# HAB.net
KiCad netlist of a schematic drawn in EAGLE
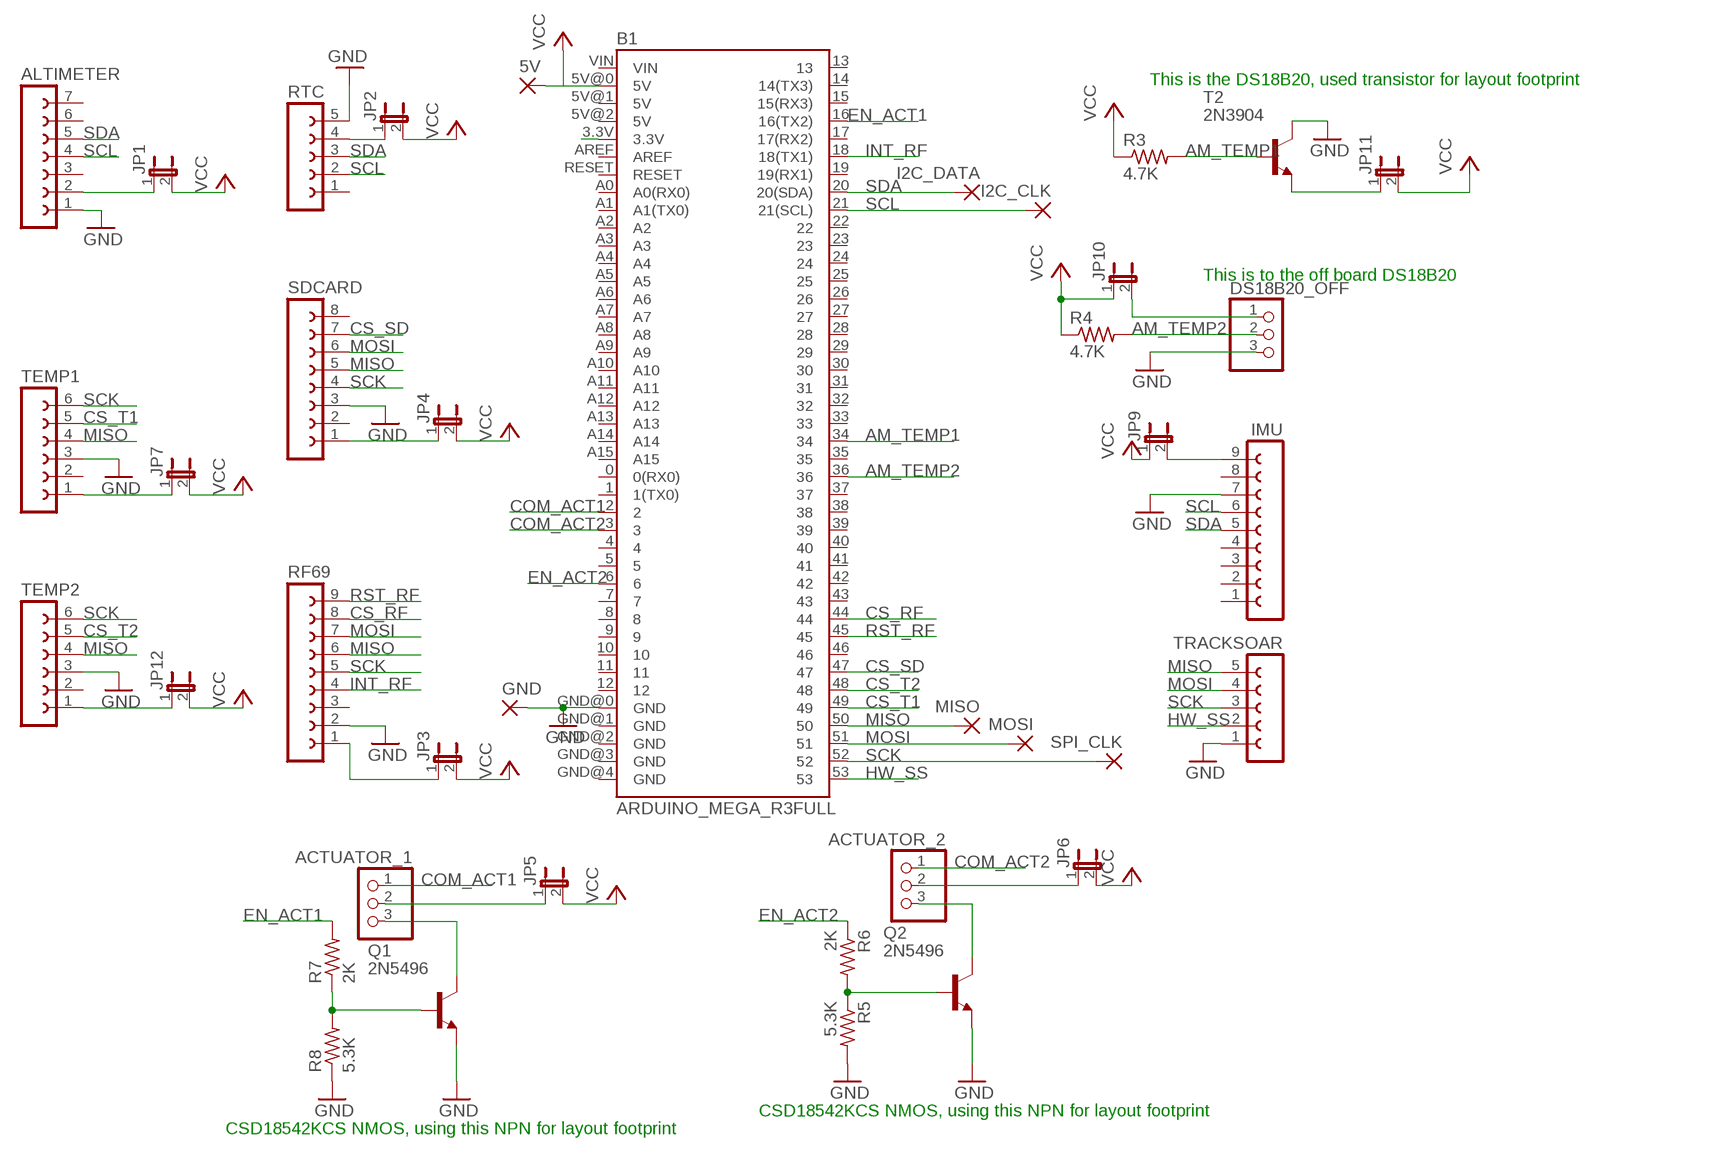
[diagram p0: schematic, sheet 1]

(export (version "E")
  (design (tool "Eeschema 10.0.6"))
  (components
    (comp (ref "5V")
      (value "1,6/0,8")
      (footprint "eagle-import:1,6_0,8")
      (libsource (lib "eagle-import") (part "1,6/0,8"))
    )
    (comp (ref "ACTUATOR_1")
      (value "PINHD-1X3")
      (footprint "eagle-import:1X03")
      (libsource (lib "eagle-import") (part "PINHD-1X3"))
    )
    (comp (ref "ACTUATOR_2")
      (value "PINHD-1X3")
      (footprint "eagle-import:1X03")
      (libsource (lib "eagle-import") (part "PINHD-1X3"))
    )
    (comp (ref "ALTIMETER")
      (value "FE07-1")
      (footprint "eagle-import:FE07")
      (libsource (lib "eagle-import") (part "FE07-1"))
    )
    (comp (ref "B1")
      (value "ARDUINO_MEGA_R3FULL")
      (footprint "eagle-import:ARDUINO_MEGA")
      (libsource (lib "eagle-import") (part "ARDUINO_MEGA_R3FULL"))
    )
    (comp (ref "DS18B20_OFF")
      (value "PINHD-1X3")
      (footprint "eagle-import:1X03")
      (libsource (lib "eagle-import") (part "PINHD-1X3"))
    )
    (comp (ref "GND")
      (value "1,6/0,8")
      (footprint "eagle-import:1,6_0,8")
      (libsource (lib "eagle-import") (part "1,6/0,8"))
    )
    (comp (ref "I2C_CLK")
      (value "1,6/0,8")
      (footprint "eagle-import:1,6_0,8")
      (libsource (lib "eagle-import") (part "1,6/0,8"))
    )
    (comp (ref "I2C_DATA")
      (value "1,6/0,8")
      (footprint "eagle-import:1,6_0,8")
      (libsource (lib "eagle-import") (part "1,6/0,8"))
    )
    (comp (ref "IMU")
      (value "FE09-1")
      (footprint "eagle-import:FE09")
      (libsource (lib "eagle-import") (part "FE09-1"))
    )
    (comp (ref "JP1")
      (value "JP1E")
      (footprint "eagle-import:JP1")
      (libsource (lib "eagle-import") (part "JP1E"))
    )
    (comp (ref "JP2")
      (value "JP1E")
      (footprint "eagle-import:JP1")
      (libsource (lib "eagle-import") (part "JP1E"))
    )
    (comp (ref "JP3")
      (value "JP1E")
      (footprint "eagle-import:JP1")
      (libsource (lib "eagle-import") (part "JP1E"))
    )
    (comp (ref "JP4")
      (value "JP1E")
      (footprint "eagle-import:JP1")
      (libsource (lib "eagle-import") (part "JP1E"))
    )
    (comp (ref "JP5")
      (value "JP1E")
      (footprint "eagle-import:JP1")
      (libsource (lib "eagle-import") (part "JP1E"))
    )
    (comp (ref "JP6")
      (value "JP1E")
      (footprint "eagle-import:JP1")
      (libsource (lib "eagle-import") (part "JP1E"))
    )
    (comp (ref "JP7")
      (value "JP1E")
      (footprint "eagle-import:JP1")
      (libsource (lib "eagle-import") (part "JP1E"))
    )
    (comp (ref "JP9")
      (value "JP1E")
      (footprint "eagle-import:JP1")
      (libsource (lib "eagle-import") (part "JP1E"))
    )
    (comp (ref "JP10")
      (value "JP1E")
      (footprint "eagle-import:JP1")
      (libsource (lib "eagle-import") (part "JP1E"))
    )
    (comp (ref "JP11")
      (value "JP1E")
      (footprint "eagle-import:JP1")
      (libsource (lib "eagle-import") (part "JP1E"))
    )
    (comp (ref "JP12")
      (value "JP1E")
      (footprint "eagle-import:JP1")
      (libsource (lib "eagle-import") (part "JP1E"))
    )
    (comp (ref "MISO")
      (value "1,6/0,8")
      (footprint "eagle-import:1,6_0,8")
      (libsource (lib "eagle-import") (part "1,6/0,8"))
    )
    (comp (ref "MOSI")
      (value "1,6/0,8")
      (footprint "eagle-import:1,6_0,8")
      (libsource (lib "eagle-import") (part "1,6/0,8"))
    )
    (comp (ref "Q1")
      (value "2N5496")
      (footprint "eagle-import:TO220")
      (libsource (lib "eagle-import") (part "2N5496"))
    )
    (comp (ref "Q2")
      (value "2N5496")
      (footprint "eagle-import:TO220")
      (libsource (lib "eagle-import") (part "2N5496"))
    )
    (comp (ref "R3")
      (value "4.7K")
      (footprint "eagle-import:0207_10")
      (libsource (lib "eagle-import") (part "R-US_0207/10"))
    )
    (comp (ref "R4")
      (value "4.7K")
      (footprint "eagle-import:0207_10")
      (libsource (lib "eagle-import") (part "R-US_0207/10"))
    )
    (comp (ref "R5")
      (value "5.3K")
      (footprint "eagle-import:0207_10")
      (libsource (lib "eagle-import") (part "R-US_0207/10"))
    )
    (comp (ref "R6")
      (value "2K")
      (footprint "eagle-import:0207_10")
      (libsource (lib "eagle-import") (part "R-US_0207/10"))
    )
    (comp (ref "R7")
      (value "2K")
      (footprint "eagle-import:0207_10")
      (libsource (lib "eagle-import") (part "R-US_0207/10"))
    )
    (comp (ref "R8")
      (value "5.3K")
      (footprint "eagle-import:0207_10")
      (libsource (lib "eagle-import") (part "R-US_0207/10"))
    )
    (comp (ref "RF69")
      (value "FE09-1")
      (footprint "eagle-import:FE09")
      (libsource (lib "eagle-import") (part "FE09-1"))
    )
    (comp (ref "RTC")
      (value "FE05-1")
      (footprint "eagle-import:FE05-1")
      (libsource (lib "eagle-import") (part "FE05-1"))
    )
    (comp (ref "SDCARD")
      (value "FE08-1")
      (footprint "eagle-import:FE08")
      (libsource (lib "eagle-import") (part "FE08-1"))
    )
    (comp (ref "SPI_CLK")
      (value "1,6/0,8")
      (footprint "eagle-import:1,6_0,8")
      (libsource (lib "eagle-import") (part "1,6/0,8"))
    )
    (comp (ref "T2")
      (value "2N3904")
      (footprint "eagle-import:TO92")
      (libsource (lib "eagle-import") (part "2N3904"))
    )
    (comp (ref "TEMP1")
      (value "FE06-1")
      (footprint "eagle-import:FE06")
      (libsource (lib "eagle-import") (part "FE06-1"))
    )
    (comp (ref "TEMP2")
      (value "FE06-1")
      (footprint "eagle-import:FE06")
      (libsource (lib "eagle-import") (part "FE06-1"))
    )
    (comp (ref "TRACKSOAR")
      (value "FE05-1")
      (footprint "eagle-import:FE05-1")
      (libsource (lib "eagle-import") (part "FE05-1"))
    )
  )
  (nets
    (net (code "1") (name "/AM_TEMP1") (class "Default")
      (node (ref "B1") (pin "34") (pinfunction "34_34") (pintype "bidirectional"))
      (node (ref "R3") (pin "2") (pinfunction "2_2") (pintype "passive"))
      (node (ref "T2") (pin "2") (pinfunction "B_2") (pintype "passive"))
    )
    (net (code "2") (name "/AM_TEMP2") (class "Default")
      (node (ref "B1") (pin "36") (pinfunction "36_36") (pintype "bidirectional"))
      (node (ref "DS18B20_OFF") (pin "2") (pinfunction "2_2") (pintype "passive"))
      (node (ref "R4") (pin "2") (pinfunction "2_2") (pintype "passive"))
    )
    (net (code "3") (name "/COM_ACT1") (class "Default")
      (node (ref "ACTUATOR_1") (pin "1") (pinfunction "1_1") (pintype "passive"))
      (node (ref "B1") (pin "2") (pinfunction "2_2") (pintype "bidirectional"))
    )
    (net (code "4") (name "/COM_ACT2") (class "Default")
      (node (ref "ACTUATOR_2") (pin "1") (pinfunction "1_1") (pintype "passive"))
      (node (ref "B1") (pin "3") (pinfunction "3_3") (pintype "bidirectional"))
    )
    (net (code "5") (name "/CS_RF") (class "Default")
      (node (ref "B1") (pin "44") (pinfunction "44_44") (pintype "bidirectional"))
      (node (ref "RF69") (pin "8") (pinfunction "8_8") (pintype "passive"))
    )
    (net (code "6") (name "/CS_SD") (class "Default")
      (node (ref "B1") (pin "47") (pinfunction "47_47") (pintype "bidirectional"))
      (node (ref "SDCARD") (pin "7") (pinfunction "7_7") (pintype "passive"))
    )
    (net (code "7") (name "/CS_T1") (class "Default")
      (node (ref "B1") (pin "49") (pinfunction "49_49") (pintype "bidirectional"))
      (node (ref "TEMP1") (pin "5") (pinfunction "5_5") (pintype "passive"))
    )
    (net (code "8") (name "/CS_T2") (class "Default")
      (node (ref "B1") (pin "48") (pinfunction "48_48") (pintype "bidirectional"))
      (node (ref "TEMP2") (pin "5") (pinfunction "5_5") (pintype "passive"))
    )
    (net (code "9") (name "/EN_ACT1") (class "Default")
      (node (ref "B1") (pin "16") (pinfunction "16(TX2)_16") (pintype "bidirectional"))
      (node (ref "R7") (pin "2") (pinfunction "2_2") (pintype "passive"))
    )
    (net (code "10") (name "/EN_ACT2") (class "Default")
      (node (ref "B1") (pin "6") (pinfunction "6_6") (pintype "bidirectional"))
      (node (ref "R6") (pin "1") (pinfunction "1_1") (pintype "passive"))
    )
    (net (code "11") (name "/HW_SS") (class "Default")
      (node (ref "B1") (pin "53") (pinfunction "53_53") (pintype "bidirectional"))
      (node (ref "TRACKSOAR") (pin "2") (pinfunction "2_2") (pintype "passive"))
    )
    (net (code "12") (name "/INT_RF") (class "Default")
      (node (ref "B1") (pin "18") (pinfunction "18(TX1)_18") (pintype "bidirectional"))
      (node (ref "RF69") (pin "4") (pinfunction "4_4") (pintype "passive"))
    )
    (net (code "13") (name "/MISO") (class "Default")
      (node (ref "B1") (pin "50") (pinfunction "50_50") (pintype "bidirectional"))
      (node (ref "MISO") (pin "1") (pinfunction "P_1") (pintype "passive"))
      (node (ref "RF69") (pin "6") (pinfunction "6_6") (pintype "passive"))
      (node (ref "SDCARD") (pin "5") (pinfunction "5_5") (pintype "passive"))
      (node (ref "TEMP1") (pin "4") (pinfunction "4_4") (pintype "passive"))
      (node (ref "TEMP2") (pin "4") (pinfunction "4_4") (pintype "passive"))
      (node (ref "TRACKSOAR") (pin "5") (pinfunction "5_5") (pintype "passive"))
    )
    (net (code "14") (name "/MOSI") (class "Default")
      (node (ref "B1") (pin "51") (pinfunction "51_51") (pintype "bidirectional"))
      (node (ref "MOSI") (pin "1") (pinfunction "P_1") (pintype "passive"))
      (node (ref "RF69") (pin "7") (pinfunction "7_7") (pintype "passive"))
      (node (ref "SDCARD") (pin "6") (pinfunction "6_6") (pintype "passive"))
      (node (ref "TRACKSOAR") (pin "4") (pinfunction "4_4") (pintype "passive"))
    )
    (net (code "15") (name "/RST_RF") (class "Default")
      (node (ref "B1") (pin "45") (pinfunction "45_45") (pintype "bidirectional"))
      (node (ref "RF69") (pin "9") (pinfunction "9_9") (pintype "passive"))
    )
    (net (code "16") (name "/SCK") (class "Default")
      (node (ref "B1") (pin "52") (pinfunction "52_52") (pintype "bidirectional"))
      (node (ref "RF69") (pin "5") (pinfunction "5_5") (pintype "passive"))
      (node (ref "SDCARD") (pin "4") (pinfunction "4_4") (pintype "passive"))
      (node (ref "SPI_CLK") (pin "1") (pinfunction "P_1") (pintype "passive"))
      (node (ref "TEMP1") (pin "6") (pinfunction "6_6") (pintype "passive"))
      (node (ref "TEMP2") (pin "6") (pinfunction "6_6") (pintype "passive"))
      (node (ref "TRACKSOAR") (pin "3") (pinfunction "3_3") (pintype "passive"))
    )
    (net (code "17") (name "/SCL") (class "Default")
      (node (ref "ALTIMETER") (pin "4") (pinfunction "4_4") (pintype "passive"))
      (node (ref "B1") (pin "21") (pinfunction "21(SCL)_21") (pintype "bidirectional"))
      (node (ref "I2C_CLK") (pin "1") (pinfunction "P_1") (pintype "passive"))
      (node (ref "IMU") (pin "6") (pinfunction "6_6") (pintype "passive"))
      (node (ref "RTC") (pin "2") (pinfunction "2_2") (pintype "passive"))
    )
    (net (code "18") (name "/SDA") (class "Default")
      (node (ref "ALTIMETER") (pin "5") (pinfunction "5_5") (pintype "passive"))
      (node (ref "B1") (pin "20") (pinfunction "20(SDA)_20") (pintype "bidirectional"))
      (node (ref "I2C_DATA") (pin "1") (pinfunction "P_1") (pintype "passive"))
      (node (ref "IMU") (pin "5") (pinfunction "5_5") (pintype "passive"))
      (node (ref "RTC") (pin "3") (pinfunction "3_3") (pintype "passive"))
    )
    (net (code "19") (name "GND") (class "Default")
      (node (ref "ALTIMETER") (pin "1") (pinfunction "1_1") (pintype "passive"))
      (node (ref "B1") (pin "GND@0") (pinfunction "GND_GND@0") (pintype "bidirectional"))
      (node (ref "DS18B20_OFF") (pin "3") (pinfunction "3_3") (pintype "passive"))
      (node (ref "GND") (pin "1") (pinfunction "P_1") (pintype "passive"))
      (node (ref "IMU") (pin "7") (pinfunction "7_7") (pintype "passive"))
      (node (ref "Q1") (pin "3") (pinfunction "E_3") (pintype "passive"))
      (node (ref "Q2") (pin "3") (pinfunction "E_3") (pintype "passive"))
      (node (ref "R5") (pin "2") (pinfunction "2_2") (pintype "passive"))
      (node (ref "R8") (pin "1") (pinfunction "1_1") (pintype "passive"))
      (node (ref "RF69") (pin "2") (pinfunction "2_2") (pintype "passive"))
      (node (ref "RTC") (pin "5") (pinfunction "5_5") (pintype "passive"))
      (node (ref "SDCARD") (pin "3") (pinfunction "3_3") (pintype "passive"))
      (node (ref "T2") (pin "1") (pinfunction "C_1") (pintype "passive"))
      (node (ref "TEMP1") (pin "3") (pinfunction "3_3") (pintype "passive"))
      (node (ref "TEMP2") (pin "3") (pinfunction "3_3") (pintype "passive"))
      (node (ref "TRACKSOAR") (pin "1") (pinfunction "1_1") (pintype "passive"))
    )
    (net (code "20") (name "Net-(ACTUATOR_1-Pad2)") (class "Default")
      (node (ref "ACTUATOR_1") (pin "2") (pinfunction "2_2") (pintype "passive"))
      (node (ref "JP5") (pin "1") (pinfunction "1_1") (pintype "passive"))
    )
    (net (code "21") (name "Net-(ACTUATOR_2-Pad2)") (class "Default")
      (node (ref "ACTUATOR_2") (pin "2") (pinfunction "2_2") (pintype "passive"))
      (node (ref "JP6") (pin "1") (pinfunction "1_1") (pintype "passive"))
    )
    (net (code "22") (name "Net-(ALTIMETER-Pad2)") (class "Default")
      (node (ref "ALTIMETER") (pin "2") (pinfunction "2_2") (pintype "passive"))
      (node (ref "JP1") (pin "1") (pinfunction "1_1") (pintype "passive"))
    )
    (net (code "23") (name "Net-(DS18B20_OFF-Pad1)") (class "Default")
      (node (ref "DS18B20_OFF") (pin "1") (pinfunction "1_1") (pintype "passive"))
      (node (ref "JP10") (pin "2") (pinfunction "2_2") (pintype "passive"))
    )
    (net (code "24") (name "Net-(IMU-Pad9)") (class "Default")
      (node (ref "IMU") (pin "9") (pinfunction "9_9") (pintype "passive"))
      (node (ref "JP9") (pin "2") (pinfunction "2_2") (pintype "passive"))
    )
    (net (code "25") (name "Net-(JP2-Pad1)") (class "Default")
      (node (ref "JP2") (pin "1") (pinfunction "1_1") (pintype "passive"))
      (node (ref "RTC") (pin "4") (pinfunction "4_4") (pintype "passive"))
    )
    (net (code "26") (name "Net-(JP3-Pad1)") (class "Default")
      (node (ref "JP3") (pin "1") (pinfunction "1_1") (pintype "passive"))
      (node (ref "RF69") (pin "1") (pinfunction "1_1") (pintype "passive"))
    )
    (net (code "27") (name "Net-(JP4-Pad1)") (class "Default")
      (node (ref "JP4") (pin "1") (pinfunction "1_1") (pintype "passive"))
      (node (ref "SDCARD") (pin "1") (pinfunction "1_1") (pintype "passive"))
    )
    (net (code "28") (name "Net-(JP7-Pad1)") (class "Default")
      (node (ref "JP7") (pin "1") (pinfunction "1_1") (pintype "passive"))
      (node (ref "TEMP1") (pin "1") (pinfunction "1_1") (pintype "passive"))
    )
    (net (code "29") (name "Net-(JP12-Pad1)") (class "Default")
      (node (ref "JP12") (pin "1") (pinfunction "1_1") (pintype "passive"))
      (node (ref "TEMP2") (pin "1") (pinfunction "1_1") (pintype "passive"))
    )
    (net (code "30") (name "Net-(Q1-B)") (class "Default")
      (node (ref "Q1") (pin "1") (pinfunction "B_1") (pintype "passive"))
      (node (ref "R7") (pin "1") (pinfunction "1_1") (pintype "passive"))
      (node (ref "R8") (pin "2") (pinfunction "2_2") (pintype "passive"))
    )
    (net (code "31") (name "Net-(Q1-C)") (class "Default")
      (node (ref "ACTUATOR_1") (pin "3") (pinfunction "3_3") (pintype "passive"))
      (node (ref "Q1") (pin "2") (pinfunction "C_2") (pintype "passive"))
    )
    (net (code "32") (name "Net-(Q2-B)") (class "Default")
      (node (ref "Q2") (pin "1") (pinfunction "B_1") (pintype "passive"))
      (node (ref "R5") (pin "1") (pinfunction "1_1") (pintype "passive"))
      (node (ref "R6") (pin "2") (pinfunction "2_2") (pintype "passive"))
    )
    (net (code "33") (name "Net-(Q2-C)") (class "Default")
      (node (ref "ACTUATOR_2") (pin "3") (pinfunction "3_3") (pintype "passive"))
      (node (ref "Q2") (pin "2") (pinfunction "C_2") (pintype "passive"))
    )
    (net (code "34") (name "Net-(T2-E)") (class "Default")
      (node (ref "JP11") (pin "1") (pinfunction "1_1") (pintype "passive"))
      (node (ref "T2") (pin "3") (pinfunction "E_3") (pintype "passive"))
    )
    (net (code "35") (name "VCC") (class "Default")
      (node (ref "5V") (pin "1") (pinfunction "P_1") (pintype "passive"))
      (node (ref "B1") (pin "5V@0") (pinfunction "5V_5V@0") (pintype "bidirectional"))
      (node (ref "JP1") (pin "2") (pinfunction "2_2") (pintype "passive"))
      (node (ref "JP10") (pin "1") (pinfunction "1_1") (pintype "passive"))
      (node (ref "JP11") (pin "2") (pinfunction "2_2") (pintype "passive"))
      (node (ref "JP12") (pin "2") (pinfunction "2_2") (pintype "passive"))
      (node (ref "JP2") (pin "2") (pinfunction "2_2") (pintype "passive"))
      (node (ref "JP3") (pin "2") (pinfunction "2_2") (pintype "passive"))
      (node (ref "JP4") (pin "2") (pinfunction "2_2") (pintype "passive"))
      (node (ref "JP5") (pin "2") (pinfunction "2_2") (pintype "passive"))
      (node (ref "JP6") (pin "2") (pinfunction "2_2") (pintype "passive"))
      (node (ref "JP7") (pin "2") (pinfunction "2_2") (pintype "passive"))
      (node (ref "JP9") (pin "1") (pinfunction "1_1") (pintype "passive"))
      (node (ref "R3") (pin "1") (pinfunction "1_1") (pintype "passive"))
      (node (ref "R4") (pin "1") (pinfunction "1_1") (pintype "passive"))
    )
    (net (code "36") (name "unconnected-(ALTIMETER-Pad3)") (class "Default")
      (node (ref "ALTIMETER") (pin "3") (pinfunction "3_3") (pintype "passive"))
    )
    (net (code "37") (name "unconnected-(ALTIMETER-Pad6)") (class "Default")
      (node (ref "ALTIMETER") (pin "6") (pinfunction "6_6") (pintype "passive"))
    )
    (net (code "38") (name "unconnected-(ALTIMETER-Pad7)") (class "Default")
      (node (ref "ALTIMETER") (pin "7") (pinfunction "7_7") (pintype "passive"))
    )
    (net (code "39") (name "unconnected-(B1-0(RX0)-Pad0)") (class "Default")
      (node (ref "B1") (pin "0") (pinfunction "0(RX0)_0") (pintype "bidirectional"))
    )
    (net (code "40") (name "unconnected-(B1-1(TX0)-Pad1)") (class "Default")
      (node (ref "B1") (pin "1") (pinfunction "1(TX0)_1") (pintype "bidirectional"))
    )
    (net (code "41") (name "unconnected-(B1-5V-Pad5V@1)") (class "Default")
      (node (ref "B1") (pin "5V@1") (pinfunction "5V_5V@1") (pintype "bidirectional"))
    )
    (net (code "42") (name "unconnected-(B1-5V-Pad5V@2)") (class "Default")
      (node (ref "B1") (pin "5V@2") (pinfunction "5V_5V@2") (pintype "bidirectional"))
    )
    (net (code "43") (name "unconnected-(B1-14(TX3)-Pad14)") (class "Default")
      (node (ref "B1") (pin "14") (pinfunction "14(TX3)_14") (pintype "bidirectional"))
    )
    (net (code "44") (name "unconnected-(B1-15(RX3)-Pad15)") (class "Default")
      (node (ref "B1") (pin "15") (pinfunction "15(RX3)_15") (pintype "bidirectional"))
    )
    (net (code "45") (name "unconnected-(B1-17(RX2)-Pad17)") (class "Default")
      (node (ref "B1") (pin "17") (pinfunction "17(RX2)_17") (pintype "bidirectional"))
    )
    (net (code "46") (name "unconnected-(B1-19(RX1)-Pad19)") (class "Default")
      (node (ref "B1") (pin "19") (pinfunction "19(RX1)_19") (pintype "bidirectional"))
    )
    (net (code "47") (name "unconnected-(B1-A0(RX0)-PadA0)") (class "Default")
      (node (ref "B1") (pin "A0") (pinfunction "A0(RX0)_A0") (pintype "bidirectional"))
    )
    (net (code "48") (name "unconnected-(B1-A1(TX0)-PadA1)") (class "Default")
      (node (ref "B1") (pin "A1") (pinfunction "A1(TX0)_A1") (pintype "bidirectional"))
    )
    (net (code "49") (name "unconnected-(B1-GND-PadGND@1)") (class "Default")
      (node (ref "B1") (pin "GND@1") (pinfunction "GND_GND@1") (pintype "bidirectional"))
    )
    (net (code "50") (name "unconnected-(B1-GND-PadGND@2)") (class "Default")
      (node (ref "B1") (pin "GND@2") (pinfunction "GND_GND@2") (pintype "bidirectional"))
    )
    (net (code "51") (name "unconnected-(B1-GND-PadGND@3)") (class "Default")
      (node (ref "B1") (pin "GND@3") (pinfunction "GND_GND@3") (pintype "bidirectional"))
    )
    (net (code "52") (name "unconnected-(B1-GND-PadGND@4)") (class "Default")
      (node (ref "B1") (pin "GND@4") (pinfunction "GND_GND@4") (pintype "bidirectional"))
    )
    (net (code "53") (name "unconnected-(B1-Pad3.3V)") (class "Default")
      (node (ref "B1") (pin "3.3V") (pinfunction "3.3V_3.3V") (pintype "bidirectional"))
    )
    (net (code "54") (name "unconnected-(B1-Pad4)") (class "Default")
      (node (ref "B1") (pin "4") (pinfunction "4_4") (pintype "bidirectional"))
    )
    (net (code "55") (name "unconnected-(B1-Pad5)") (class "Default")
      (node (ref "B1") (pin "5") (pinfunction "5_5") (pintype "bidirectional"))
    )
    (net (code "56") (name "unconnected-(B1-Pad7)") (class "Default")
      (node (ref "B1") (pin "7") (pinfunction "7_7") (pintype "bidirectional"))
    )
    (net (code "57") (name "unconnected-(B1-Pad8)") (class "Default")
      (node (ref "B1") (pin "8") (pinfunction "8_8") (pintype "bidirectional"))
    )
    (net (code "58") (name "unconnected-(B1-Pad9)") (class "Default")
      (node (ref "B1") (pin "9") (pinfunction "9_9") (pintype "bidirectional"))
    )
    (net (code "59") (name "unconnected-(B1-Pad10)") (class "Default")
      (node (ref "B1") (pin "10") (pinfunction "10_10") (pintype "bidirectional"))
    )
    (net (code "60") (name "unconnected-(B1-Pad11)") (class "Default")
      (node (ref "B1") (pin "11") (pinfunction "11_11") (pintype "bidirectional"))
    )
    (net (code "61") (name "unconnected-(B1-Pad12)") (class "Default")
      (node (ref "B1") (pin "12") (pinfunction "12_12") (pintype "bidirectional"))
    )
    (net (code "62") (name "unconnected-(B1-Pad13)") (class "Default")
      (node (ref "B1") (pin "13") (pinfunction "13_13") (pintype "bidirectional"))
    )
    (net (code "63") (name "unconnected-(B1-Pad22)") (class "Default")
      (node (ref "B1") (pin "22") (pinfunction "22_22") (pintype "bidirectional"))
    )
    (net (code "64") (name "unconnected-(B1-Pad23)") (class "Default")
      (node (ref "B1") (pin "23") (pinfunction "23_23") (pintype "bidirectional"))
    )
    (net (code "65") (name "unconnected-(B1-Pad24)") (class "Default")
      (node (ref "B1") (pin "24") (pinfunction "24_24") (pintype "bidirectional"))
    )
    (net (code "66") (name "unconnected-(B1-Pad25)") (class "Default")
      (node (ref "B1") (pin "25") (pinfunction "25_25") (pintype "bidirectional"))
    )
    (net (code "67") (name "unconnected-(B1-Pad26)") (class "Default")
      (node (ref "B1") (pin "26") (pinfunction "26_26") (pintype "bidirectional"))
    )
    (net (code "68") (name "unconnected-(B1-Pad27)") (class "Default")
      (node (ref "B1") (pin "27") (pinfunction "27_27") (pintype "bidirectional"))
    )
    (net (code "69") (name "unconnected-(B1-Pad28)") (class "Default")
      (node (ref "B1") (pin "28") (pinfunction "28_28") (pintype "bidirectional"))
    )
    (net (code "70") (name "unconnected-(B1-Pad29)") (class "Default")
      (node (ref "B1") (pin "29") (pinfunction "29_29") (pintype "bidirectional"))
    )
    (net (code "71") (name "unconnected-(B1-Pad30)") (class "Default")
      (node (ref "B1") (pin "30") (pinfunction "30_30") (pintype "bidirectional"))
    )
    (net (code "72") (name "unconnected-(B1-Pad31)") (class "Default")
      (node (ref "B1") (pin "31") (pinfunction "31_31") (pintype "bidirectional"))
    )
    (net (code "73") (name "unconnected-(B1-Pad32)") (class "Default")
      (node (ref "B1") (pin "32") (pinfunction "32_32") (pintype "bidirectional"))
    )
    (net (code "74") (name "unconnected-(B1-Pad33)") (class "Default")
      (node (ref "B1") (pin "33") (pinfunction "33_33") (pintype "bidirectional"))
    )
    (net (code "75") (name "unconnected-(B1-Pad35)") (class "Default")
      (node (ref "B1") (pin "35") (pinfunction "35_35") (pintype "bidirectional"))
    )
    (net (code "76") (name "unconnected-(B1-Pad37)") (class "Default")
      (node (ref "B1") (pin "37") (pinfunction "37_37") (pintype "bidirectional"))
    )
    (net (code "77") (name "unconnected-(B1-Pad38)") (class "Default")
      (node (ref "B1") (pin "38") (pinfunction "38_38") (pintype "bidirectional"))
    )
    (net (code "78") (name "unconnected-(B1-Pad39)") (class "Default")
      (node (ref "B1") (pin "39") (pinfunction "39_39") (pintype "bidirectional"))
    )
    (net (code "79") (name "unconnected-(B1-Pad40)") (class "Default")
      (node (ref "B1") (pin "40") (pinfunction "40_40") (pintype "bidirectional"))
    )
    (net (code "80") (name "unconnected-(B1-Pad41)") (class "Default")
      (node (ref "B1") (pin "41") (pinfunction "41_41") (pintype "bidirectional"))
    )
    (net (code "81") (name "unconnected-(B1-Pad42)") (class "Default")
      (node (ref "B1") (pin "42") (pinfunction "42_42") (pintype "bidirectional"))
    )
    (net (code "82") (name "unconnected-(B1-Pad43)") (class "Default")
      (node (ref "B1") (pin "43") (pinfunction "43_43") (pintype "bidirectional"))
    )
    (net (code "83") (name "unconnected-(B1-Pad46)") (class "Default")
      (node (ref "B1") (pin "46") (pinfunction "46_46") (pintype "bidirectional"))
    )
    (net (code "84") (name "unconnected-(B1-PadA2)") (class "Default")
      (node (ref "B1") (pin "A2") (pinfunction "A2_A2") (pintype "bidirectional"))
    )
    (net (code "85") (name "unconnected-(B1-PadA3)") (class "Default")
      (node (ref "B1") (pin "A3") (pinfunction "A3_A3") (pintype "bidirectional"))
    )
    (net (code "86") (name "unconnected-(B1-PadA4)") (class "Default")
      (node (ref "B1") (pin "A4") (pinfunction "A4_A4") (pintype "bidirectional"))
    )
    (net (code "87") (name "unconnected-(B1-PadA5)") (class "Default")
      (node (ref "B1") (pin "A5") (pinfunction "A5_A5") (pintype "bidirectional"))
    )
    (net (code "88") (name "unconnected-(B1-PadA6)") (class "Default")
      (node (ref "B1") (pin "A6") (pinfunction "A6_A6") (pintype "bidirectional"))
    )
    (net (code "89") (name "unconnected-(B1-PadA7)") (class "Default")
      (node (ref "B1") (pin "A7") (pinfunction "A7_A7") (pintype "bidirectional"))
    )
    (net (code "90") (name "unconnected-(B1-PadA8)") (class "Default")
      (node (ref "B1") (pin "A8") (pinfunction "A8_A8") (pintype "bidirectional"))
    )
    (net (code "91") (name "unconnected-(B1-PadA9)") (class "Default")
      (node (ref "B1") (pin "A9") (pinfunction "A9_A9") (pintype "bidirectional"))
    )
    (net (code "92") (name "unconnected-(B1-PadA10)") (class "Default")
      (node (ref "B1") (pin "A10") (pinfunction "A10_A10") (pintype "bidirectional"))
    )
    (net (code "93") (name "unconnected-(B1-PadA11)") (class "Default")
      (node (ref "B1") (pin "A11") (pinfunction "A11_A11") (pintype "bidirectional"))
    )
    (net (code "94") (name "unconnected-(B1-PadA12)") (class "Default")
      (node (ref "B1") (pin "A12") (pinfunction "A12_A12") (pintype "bidirectional"))
    )
    (net (code "95") (name "unconnected-(B1-PadA13)") (class "Default")
      (node (ref "B1") (pin "A13") (pinfunction "A13_A13") (pintype "bidirectional"))
    )
    (net (code "96") (name "unconnected-(B1-PadA14)") (class "Default")
      (node (ref "B1") (pin "A14") (pinfunction "A14_A14") (pintype "bidirectional"))
    )
    (net (code "97") (name "unconnected-(B1-PadA15)") (class "Default")
      (node (ref "B1") (pin "A15") (pinfunction "A15_A15") (pintype "bidirectional"))
    )
    (net (code "98") (name "unconnected-(B1-PadAREF)") (class "Default")
      (node (ref "B1") (pin "AREF") (pinfunction "AREF_AREF") (pintype "bidirectional"))
    )
    (net (code "99") (name "unconnected-(B1-PadRESET)") (class "Default")
      (node (ref "B1") (pin "RESET") (pinfunction "RESET_RESET") (pintype "bidirectional"))
    )
    (net (code "100") (name "unconnected-(B1-PadVIN)") (class "Default")
      (node (ref "B1") (pin "VIN") (pinfunction "VIN_VIN") (pintype "bidirectional"))
    )
    (net (code "101") (name "unconnected-(IMU-Pad1)") (class "Default")
      (node (ref "IMU") (pin "1") (pinfunction "1_1") (pintype "passive"))
    )
    (net (code "102") (name "unconnected-(IMU-Pad2)") (class "Default")
      (node (ref "IMU") (pin "2") (pinfunction "2_2") (pintype "passive"))
    )
    (net (code "103") (name "unconnected-(IMU-Pad3)") (class "Default")
      (node (ref "IMU") (pin "3") (pinfunction "3_3") (pintype "passive"))
    )
    (net (code "104") (name "unconnected-(IMU-Pad4)") (class "Default")
      (node (ref "IMU") (pin "4") (pinfunction "4_4") (pintype "passive"))
    )
    (net (code "105") (name "unconnected-(IMU-Pad8)") (class "Default")
      (node (ref "IMU") (pin "8") (pinfunction "8_8") (pintype "passive"))
    )
    (net (code "106") (name "unconnected-(RF69-Pad3)") (class "Default")
      (node (ref "RF69") (pin "3") (pinfunction "3_3") (pintype "passive"))
    )
    (net (code "107") (name "unconnected-(RTC-Pad1)") (class "Default")
      (node (ref "RTC") (pin "1") (pinfunction "1_1") (pintype "passive"))
    )
    (net (code "108") (name "unconnected-(SDCARD-Pad2)") (class "Default")
      (node (ref "SDCARD") (pin "2") (pinfunction "2_2") (pintype "passive"))
    )
    (net (code "109") (name "unconnected-(SDCARD-Pad8)") (class "Default")
      (node (ref "SDCARD") (pin "8") (pinfunction "8_8") (pintype "passive"))
    )
    (net (code "110") (name "unconnected-(TEMP1-Pad2)") (class "Default")
      (node (ref "TEMP1") (pin "2") (pinfunction "2_2") (pintype "passive"))
    )
    (net (code "111") (name "unconnected-(TEMP2-Pad2)") (class "Default")
      (node (ref "TEMP2") (pin "2") (pinfunction "2_2") (pintype "passive"))
    )
  )
)
